# Clocks.net
KiCad netlist of a schematic drawn in Altium Designer
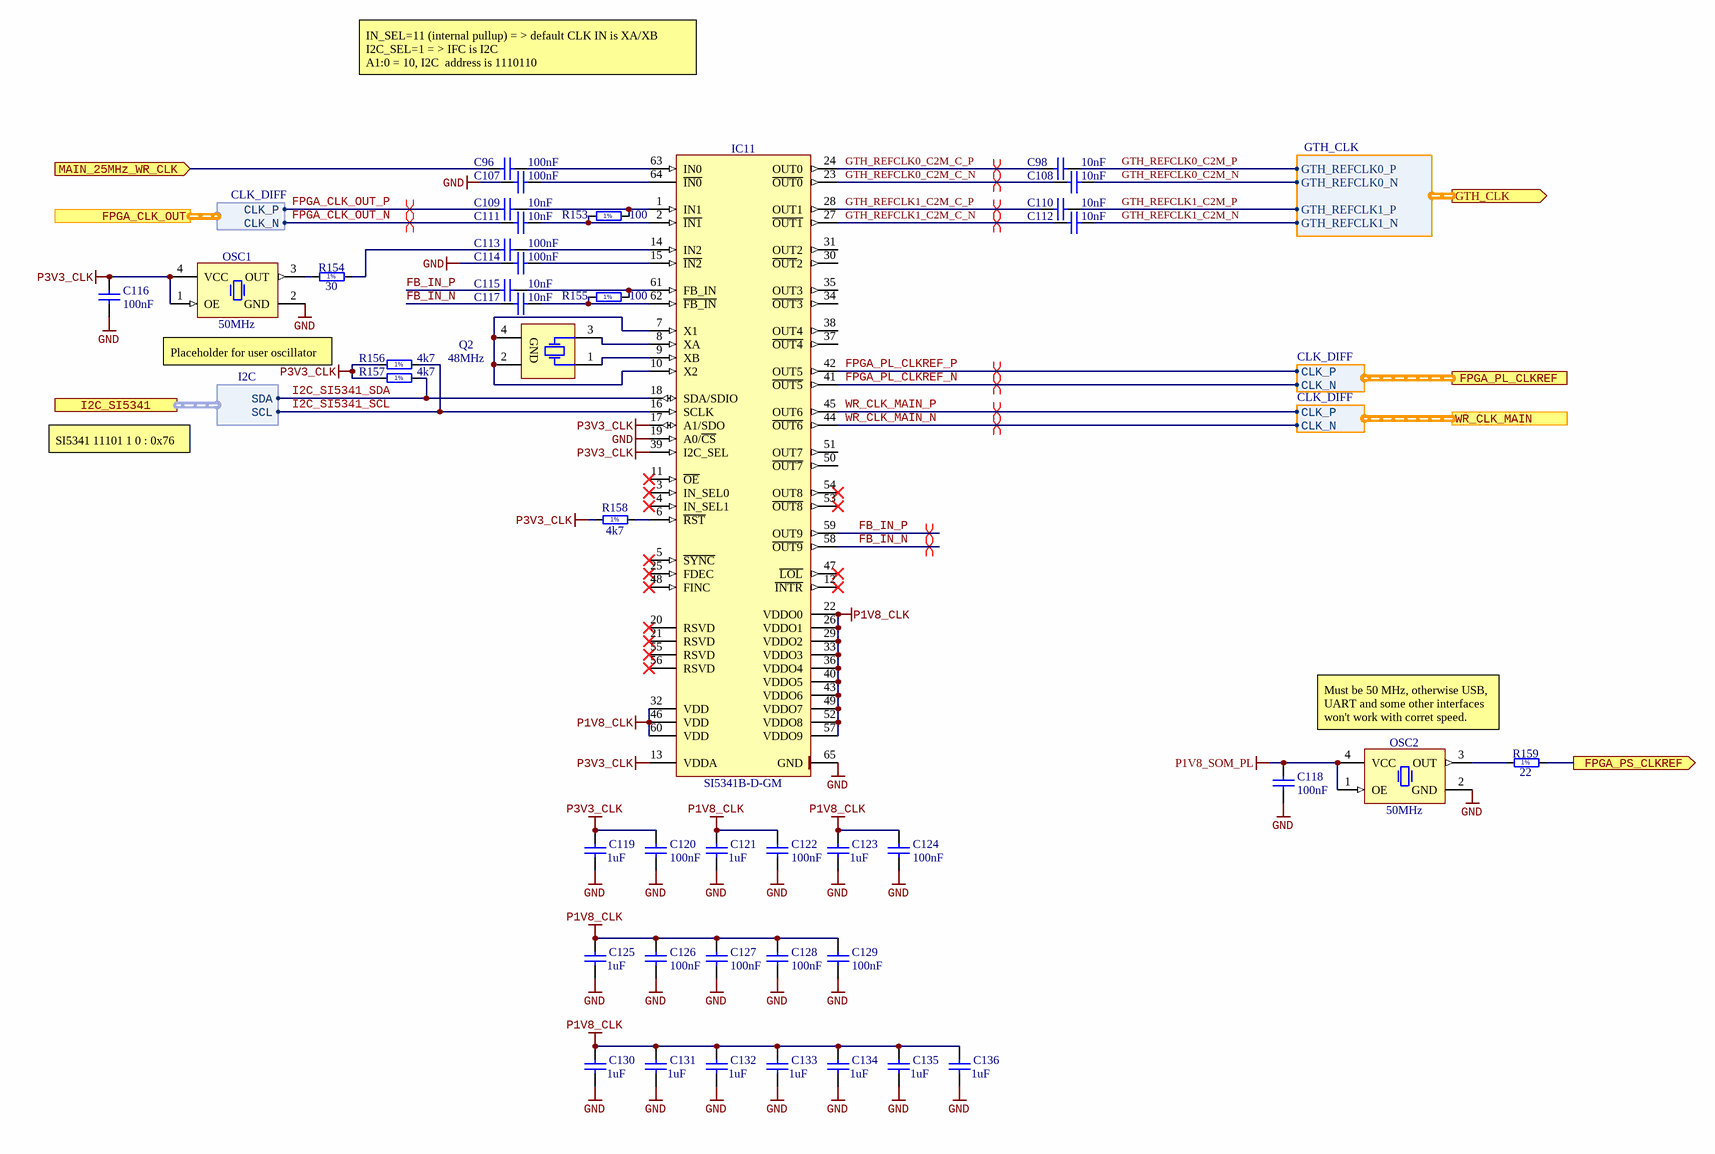
[diagram p0: Clocks.SchDoc]

(export (version "E")
  (design (tool "Eeschema 10.0.6"))
  (components
    (comp (ref "C96")
      (value "100nF")
      (footprint "CAPC1005X55N")
      (description "Non-polarised capacitor")
      (fields
        (field (name "PART NUMBER") "CC0402_100NF_16V_10%_X5R")
        (field (name "VOLTAGE") "16V")
        (field (name "AUTHOR") "CERN DEM JLC")
      )
      (libsource (lib "Capacitors") (part "Capacitor - non polarized"))
    )
    (comp (ref "C98")
      (value "10nF")
      (footprint "CAPC1005X55N")
      (description "Non-polarised capacitor")
      (fields
        (field (name "PART NUMBER") "CC0402_10NF_16V_10%_X7R")
        (field (name "VOLTAGE") "16V")
        (field (name "AUTHOR") "CERN DEM JLC")
      )
      (libsource (lib "Capacitors") (part "Capacitor - non polarized"))
    )
    (comp (ref "C107")
      (value "100nF")
      (footprint "CAPC1005X55N")
      (description "Non-polarised capacitor")
      (fields
        (field (name "PART NUMBER") "CC0402_100NF_16V_10%_X5R")
        (field (name "VOLTAGE") "16V")
        (field (name "AUTHOR") "CERN DEM JLC")
      )
      (libsource (lib "Capacitors") (part "Capacitor - non polarized"))
    )
    (comp (ref "C108")
      (value "10nF")
      (footprint "CAPC1005X55N")
      (description "Non-polarised capacitor")
      (fields
        (field (name "PART NUMBER") "CC0402_10NF_16V_10%_X7R")
        (field (name "VOLTAGE") "16V")
        (field (name "AUTHOR") "CERN DEM JLC")
      )
      (libsource (lib "Capacitors") (part "Capacitor - non polarized"))
    )
    (comp (ref "C109")
      (value "10nF")
      (footprint "CAPC1005X55N")
      (description "Non-polarised capacitor")
      (fields
        (field (name "PART NUMBER") "CC0402_10NF_16V_10%_X7R")
        (field (name "VOLTAGE") "16V")
        (field (name "AUTHOR") "CERN DEM JLC")
      )
      (libsource (lib "Capacitors") (part "Capacitor - non polarized"))
    )
    (comp (ref "C110")
      (value "10nF")
      (footprint "CAPC1005X55N")
      (description "Non-polarised capacitor")
      (fields
        (field (name "PART NUMBER") "CC0402_10NF_16V_10%_X7R")
        (field (name "VOLTAGE") "16V")
        (field (name "AUTHOR") "CERN DEM JLC")
      )
      (libsource (lib "Capacitors") (part "Capacitor - non polarized"))
    )
    (comp (ref "C111")
      (value "10nF")
      (footprint "CAPC1005X55N")
      (description "Non-polarised capacitor")
      (fields
        (field (name "PART NUMBER") "CC0402_10NF_16V_10%_X7R")
        (field (name "VOLTAGE") "16V")
        (field (name "AUTHOR") "CERN DEM JLC")
      )
      (libsource (lib "Capacitors") (part "Capacitor - non polarized"))
    )
    (comp (ref "C112")
      (value "10nF")
      (footprint "CAPC1005X55N")
      (description "Non-polarised capacitor")
      (fields
        (field (name "PART NUMBER") "CC0402_10NF_16V_10%_X7R")
        (field (name "VOLTAGE") "16V")
        (field (name "AUTHOR") "CERN DEM JLC")
      )
      (libsource (lib "Capacitors") (part "Capacitor - non polarized"))
    )
    (comp (ref "C113")
      (value "100nF")
      (footprint "CAPC1005X55N")
      (description "Non-polarised capacitor")
      (fields
        (field (name "PART NUMBER") "CC0402_100NF_16V_10%_X5R")
        (field (name "VOLTAGE") "16V")
        (field (name "AUTHOR") "CERN DEM JLC")
      )
      (libsource (lib "Capacitors") (part "Capacitor - non polarized"))
    )
    (comp (ref "C114")
      (value "100nF")
      (footprint "CAPC1005X55N")
      (description "Non-polarised capacitor")
      (fields
        (field (name "PART NUMBER") "CC0402_100NF_16V_10%_X5R")
        (field (name "VOLTAGE") "16V")
        (field (name "AUTHOR") "CERN DEM JLC")
      )
      (libsource (lib "Capacitors") (part "Capacitor - non polarized"))
    )
    (comp (ref "C115")
      (value "10nF")
      (footprint "CAPC1005X55N")
      (description "Non-polarised capacitor")
      (fields
        (field (name "PART NUMBER") "CC0402_10NF_16V_10%_X7R")
        (field (name "VOLTAGE") "16V")
        (field (name "AUTHOR") "CERN DEM JLC")
      )
      (libsource (lib "Capacitors") (part "Capacitor - non polarized"))
    )
    (comp (ref "C116")
      (value "100nF")
      (footprint "CAPC1005X55N")
      (description "Non-polarised capacitor")
      (fields
        (field (name "PART NUMBER") "CC0402_100NF_16V_10%_X5R")
        (field (name "VOLTAGE") "16V")
        (field (name "AUTHOR") "CERN DEM JLC")
      )
      (libsource (lib "Capacitors") (part "Capacitor - non polarized"))
    )
    (comp (ref "C117")
      (value "10nF")
      (footprint "CAPC1005X55N")
      (description "Non-polarised capacitor")
      (fields
        (field (name "PART NUMBER") "CC0402_10NF_16V_10%_X7R")
        (field (name "VOLTAGE") "16V")
        (field (name "AUTHOR") "CERN DEM JLC")
      )
      (libsource (lib "Capacitors") (part "Capacitor - non polarized"))
    )
    (comp (ref "C118")
      (value "100nF")
      (footprint "CAPC1005X55N")
      (description "Non-polarised capacitor")
      (fields
        (field (name "PART NUMBER") "CC0402_100NF_16V_10%_X5R")
        (field (name "VOLTAGE") "16V")
        (field (name "AUTHOR") "CERN DEM JLC")
      )
      (libsource (lib "Capacitors") (part "Capacitor - non polarized"))
    )
    (comp (ref "C119")
      (value "1uF")
      (footprint "CAPC1005X55N")
      (description "Non-polarised capacitor")
      (fields
        (field (name "PART NUMBER") "CC0402_1UF_16V_10%_X5R")
        (field (name "VOLTAGE") "16V")
        (field (name "AUTHOR") "CERN DEM JLC")
      )
      (libsource (lib "Capacitors") (part "Capacitor - non polarized"))
    )
    (comp (ref "C120")
      (value "100nF")
      (footprint "CAPC1005X55N")
      (description "Non-polarised capacitor")
      (fields
        (field (name "PART NUMBER") "CC0402_100NF_16V_10%_X5R")
        (field (name "VOLTAGE") "16V")
        (field (name "AUTHOR") "CERN DEM JLC")
      )
      (libsource (lib "Capacitors") (part "Capacitor - non polarized"))
    )
    (comp (ref "C121")
      (value "1uF")
      (footprint "CAPC1005X55N")
      (description "Non-polarised capacitor")
      (fields
        (field (name "PART NUMBER") "CC0402_1UF_16V_10%_X5R")
        (field (name "VOLTAGE") "16V")
        (field (name "AUTHOR") "CERN DEM JLC")
      )
      (libsource (lib "Capacitors") (part "Capacitor - non polarized"))
    )
    (comp (ref "C122")
      (value "100nF")
      (footprint "CAPC1005X55N")
      (description "Non-polarised capacitor")
      (fields
        (field (name "PART NUMBER") "CC0402_100NF_16V_10%_X5R")
        (field (name "VOLTAGE") "16V")
        (field (name "AUTHOR") "CERN DEM JLC")
      )
      (libsource (lib "Capacitors") (part "Capacitor - non polarized"))
    )
    (comp (ref "C123")
      (value "1uF")
      (footprint "CAPC1005X55N")
      (description "Non-polarised capacitor")
      (fields
        (field (name "PART NUMBER") "CC0402_1UF_16V_10%_X5R")
        (field (name "VOLTAGE") "16V")
        (field (name "AUTHOR") "CERN DEM JLC")
      )
      (libsource (lib "Capacitors") (part "Capacitor - non polarized"))
    )
    (comp (ref "C124")
      (value "100nF")
      (footprint "CAPC1005X55N")
      (description "Non-polarised capacitor")
      (fields
        (field (name "PART NUMBER") "CC0402_100NF_16V_10%_X5R")
        (field (name "VOLTAGE") "16V")
        (field (name "AUTHOR") "CERN DEM JLC")
      )
      (libsource (lib "Capacitors") (part "Capacitor - non polarized"))
    )
    (comp (ref "C125")
      (value "1uF")
      (footprint "CAPC1005X55N")
      (description "Non-polarised capacitor")
      (fields
        (field (name "PART NUMBER") "CC0402_1UF_16V_10%_X5R")
        (field (name "VOLTAGE") "16V")
        (field (name "AUTHOR") "CERN DEM JLC")
      )
      (libsource (lib "Capacitors") (part "Capacitor - non polarized"))
    )
    (comp (ref "C126")
      (value "100nF")
      (footprint "CAPC1005X55N")
      (description "Non-polarised capacitor")
      (fields
        (field (name "PART NUMBER") "CC0402_100NF_16V_10%_X5R")
        (field (name "VOLTAGE") "16V")
        (field (name "AUTHOR") "CERN DEM JLC")
      )
      (libsource (lib "Capacitors") (part "Capacitor - non polarized"))
    )
    (comp (ref "C127")
      (value "100nF")
      (footprint "CAPC1005X55N")
      (description "Non-polarised capacitor")
      (fields
        (field (name "PART NUMBER") "CC0402_100NF_16V_10%_X5R")
        (field (name "VOLTAGE") "16V")
        (field (name "AUTHOR") "CERN DEM JLC")
      )
      (libsource (lib "Capacitors") (part "Capacitor - non polarized"))
    )
    (comp (ref "C128")
      (value "100nF")
      (footprint "CAPC1005X55N")
      (description "Non-polarised capacitor")
      (fields
        (field (name "PART NUMBER") "CC0402_100NF_16V_10%_X5R")
        (field (name "VOLTAGE") "16V")
        (field (name "AUTHOR") "CERN DEM JLC")
      )
      (libsource (lib "Capacitors") (part "Capacitor - non polarized"))
    )
    (comp (ref "C129")
      (value "100nF")
      (footprint "CAPC1005X55N")
      (description "Non-polarised capacitor")
      (fields
        (field (name "PART NUMBER") "CC0402_100NF_16V_10%_X5R")
        (field (name "VOLTAGE") "16V")
        (field (name "AUTHOR") "CERN DEM JLC")
      )
      (libsource (lib "Capacitors") (part "Capacitor - non polarized"))
    )
    (comp (ref "C130")
      (value "1uF")
      (footprint "CAPC1005X55N")
      (description "Non-polarised capacitor")
      (fields
        (field (name "PART NUMBER") "CC0402_1UF_16V_10%_X5R")
        (field (name "VOLTAGE") "16V")
        (field (name "AUTHOR") "CERN DEM JLC")
      )
      (libsource (lib "Capacitors") (part "Capacitor - non polarized"))
    )
    (comp (ref "C131")
      (value "1uF")
      (footprint "CAPC1005X55N")
      (description "Non-polarised capacitor")
      (fields
        (field (name "PART NUMBER") "CC0402_1UF_16V_10%_X5R")
        (field (name "VOLTAGE") "16V")
        (field (name "AUTHOR") "CERN DEM JLC")
      )
      (libsource (lib "Capacitors") (part "Capacitor - non polarized"))
    )
    (comp (ref "C132")
      (value "1uF")
      (footprint "CAPC1005X55N")
      (description "Non-polarised capacitor")
      (fields
        (field (name "PART NUMBER") "CC0402_1UF_16V_10%_X5R")
        (field (name "VOLTAGE") "16V")
        (field (name "AUTHOR") "CERN DEM JLC")
      )
      (libsource (lib "Capacitors") (part "Capacitor - non polarized"))
    )
    (comp (ref "C133")
      (value "1uF")
      (footprint "CAPC1005X55N")
      (description "Non-polarised capacitor")
      (fields
        (field (name "PART NUMBER") "CC0402_1UF_16V_10%_X5R")
        (field (name "VOLTAGE") "16V")
        (field (name "AUTHOR") "CERN DEM JLC")
      )
      (libsource (lib "Capacitors") (part "Capacitor - non polarized"))
    )
    (comp (ref "C134")
      (value "1uF")
      (footprint "CAPC1005X55N")
      (description "Non-polarised capacitor")
      (fields
        (field (name "PART NUMBER") "CC0402_1UF_16V_10%_X5R")
        (field (name "VOLTAGE") "16V")
        (field (name "AUTHOR") "CERN DEM JLC")
      )
      (libsource (lib "Capacitors") (part "Capacitor - non polarized"))
    )
    (comp (ref "C135")
      (value "1uF")
      (footprint "CAPC1005X55N")
      (description "Non-polarised capacitor")
      (fields
        (field (name "PART NUMBER") "CC0402_1UF_16V_10%_X5R")
        (field (name "VOLTAGE") "16V")
        (field (name "AUTHOR") "CERN DEM JLC")
      )
      (libsource (lib "Capacitors") (part "Capacitor - non polarized"))
    )
    (comp (ref "C136")
      (value "1uF")
      (footprint "CAPC1005X55N")
      (description "Non-polarised capacitor")
      (fields
        (field (name "PART NUMBER") "CC0402_1UF_16V_10%_X5R")
        (field (name "VOLTAGE") "16V")
        (field (name "AUTHOR") "CERN DEM JLC")
      )
      (libsource (lib "Capacitors") (part "Capacitor - non polarized"))
    )
    (comp (ref "IC11")
      (value "SI5341B-D-GM")
      (footprint "QFN50P900X900X90-65N-S530")
      (description "Low-Jitter, 10-Output, Any-Frequency, Any-Output Clock Generator")
      (fields (field (name "MANUFACTURER") "SILICON LABS") (field (name "AUTHOR") "CERN DEM BC"))
      (libsource (lib "ICs And Semiconductors") (part "SI5341"))
    )
    (comp (ref "OSC1")
      (value "50MHz")
      (footprint "OSC_EPSON_SG-8018CE")
      (description "Oscillator 4 pins 1=OE 2=GND 3=OUT 4=VCC")
      (fields
        (field (name "PART NUMBER") "OSC_50MHZ_EPSON_SG-8018CE")
        (field (name "MANUFACTURER") "EPSON SEIKO")
        (field (name "AUTHOR") "CERN DEM BC")
      )
      (libsource (lib "ICs And Semiconductors") (part "Oscillator 1OE 2GND 3OUT 4VCC"))
    )
    (comp (ref "OSC2")
      (value "50MHz")
      (footprint "OSC_EPSON_SG-8018CE")
      (description "Oscillator 4 pins 1=OE 2=GND 3=OUT 4=VCC")
      (fields
        (field (name "PART NUMBER") "OSC_50MHZ_EPSON_SG-8018CE")
        (field (name "MANUFACTURER") "EPSON SEIKO")
        (field (name "AUTHOR") "CERN DEM BC")
      )
      (libsource (lib "ICs And Semiconductors") (part "Oscillator 1OE 2GND 3OUT 4VCC"))
    )
    (comp (ref "Q2")
      (value "48MHz")
      (footprint "XTAL_TXC_7M")
      (description "Crystal 4 pins 1=XTAL Control 2=GND3=XTAL 4=GND")
      (fields
        (field (name "PART NUMBER") "XTAL_48MHZ_TXC_7M-48.000MAHV")
        (field (name "MANUFACTURER") "TXC CORPORATION")
        (field (name "AUTHOR") "CERN DEM MR")
      )
      (libsource (lib "ICs And Semiconductors") (part "Quartz Crystal 1X 2GND 3X 4GND"))
    )
    (comp (ref "R153")
      (value "100")
      (footprint "RESC1005X40N")
      (description "Resistor - 1%")
      (fields
        (field (name "PART NUMBER") "R0402_100R_1%_0.0625W_100PPM")
        (field (name "POWER") "0.0625W")
        (field (name "AUTHOR") "CERN DEM JLC")
      )
      (libsource (lib "Resistors") (part "Resistor - 1%"))
    )
    (comp (ref "R154")
      (value "30")
      (footprint "RESC1005X40N")
      (description "Resistor - 1%")
      (fields
        (field (name "PART NUMBER") "R0402_30R_1%_0.0625W_100PPM")
        (field (name "POWER") "0.0625W")
        (field (name "AUTHOR") "CERN DEM JLC")
      )
      (libsource (lib "Resistors") (part "Resistor - 1%"))
    )
    (comp (ref "R155")
      (value "100")
      (footprint "RESC1005X40N")
      (description "Resistor - 1%")
      (fields
        (field (name "PART NUMBER") "R0402_100R_1%_0.0625W_100PPM")
        (field (name "POWER") "0.0625W")
        (field (name "AUTHOR") "CERN DEM JLC")
      )
      (libsource (lib "Resistors") (part "Resistor - 1%"))
    )
    (comp (ref "R156")
      (value "4k7")
      (footprint "RESC1005X40N")
      (description "Resistor - 1%")
      (fields
        (field (name "PART NUMBER") "R0402_4K7_1%_0.0625W_100PPM")
        (field (name "POWER") "0.0625W")
        (field (name "AUTHOR") "CERN DEM JLC")
      )
      (libsource (lib "Resistors") (part "Resistor - 1%"))
    )
    (comp (ref "R157")
      (value "4k7")
      (footprint "RESC1005X40N")
      (description "Resistor - 1%")
      (fields
        (field (name "PART NUMBER") "R0402_4K7_1%_0.0625W_100PPM")
        (field (name "POWER") "0.0625W")
        (field (name "AUTHOR") "CERN DEM JLC")
      )
      (libsource (lib "Resistors") (part "Resistor - 1%"))
    )
    (comp (ref "R158")
      (value "4k7")
      (footprint "RESC1005X40N")
      (description "Resistor - 1%")
      (fields
        (field (name "PART NUMBER") "R0402_4K7_1%_0.0625W_100PPM")
        (field (name "POWER") "0.0625W")
        (field (name "AUTHOR") "CERN DEM JLC")
      )
      (libsource (lib "Resistors") (part "Resistor - 1%"))
    )
    (comp (ref "R159")
      (value "22")
      (footprint "RESC1005X40N")
      (description "Resistor - 1%")
      (fields
        (field (name "PART NUMBER") "R0402_22R_1%_0.0625W_100PPM")
        (field (name "POWER") "0.0625W")
        (field (name "AUTHOR") "CERN DEM JLC")
      )
      (libsource (lib "Resistors") (part "Resistor - 1%"))
    )
  )
  (nets
    (net (code "5") (name "/FB_IN_N") (class "Default")
      (node (ref "C117") (pin "2") (pinfunction "2_2") (pintype "passive"))
      (node (ref "IC11") (pin "58") (pinfunction "~{OUT9}_58") (pintype "output"))
    )
    (net (code "6") (name "/FB_IN_P") (class "Default")
      (node (ref "C115") (pin "2") (pinfunction "2_2") (pintype "passive"))
      (node (ref "IC11") (pin "59") (pinfunction "OUT9_59") (pintype "output"))
    )
    (net (code "7") (name "/FPGA_CLK_OUT_N") (class "Default")
      (node (ref "C111") (pin "2") (pinfunction "2_2") (pintype "passive"))
    )
    (net (code "8") (name "/FPGA_CLK_OUT_P") (class "Default")
      (node (ref "C109") (pin "2") (pinfunction "2_2") (pintype "passive"))
    )
    (net (code "9") (name "/FPGA_PL_CLKREF_N") (class "Default")
      (node (ref "IC11") (pin "41") (pinfunction "~{OUT5}_41") (pintype "output"))
    )
    (net (code "10") (name "/FPGA_PL_CLKREF_P") (class "Default")
      (node (ref "IC11") (pin "42") (pinfunction "OUT5_42") (pintype "output"))
    )
    (net (code "11") (name "/FPGA_PS_CLKREF") (class "Default")
      (node (ref "R159") (pin "2") (pinfunction "2_2") (pintype "passive"))
    )
    (net (code "12") (name "/GTH_REFCLK0_C2M_C_N") (class "Default")
      (node (ref "C108") (pin "2") (pinfunction "2_2") (pintype "passive"))
      (node (ref "IC11") (pin "23") (pinfunction "~{OUT0}_23") (pintype "output"))
    )
    (net (code "13") (name "/GTH_REFCLK0_C2M_C_P") (class "Default")
      (node (ref "C98") (pin "2") (pinfunction "2_2") (pintype "passive"))
      (node (ref "IC11") (pin "24") (pinfunction "OUT0_24") (pintype "output"))
    )
    (net (code "14") (name "/GTH_REFCLK0_C2M_N") (class "Default")
      (node (ref "C108") (pin "1") (pinfunction "1_1") (pintype "passive"))
    )
    (net (code "15") (name "/GTH_REFCLK0_C2M_P") (class "Default")
      (node (ref "C98") (pin "1") (pinfunction "1_1") (pintype "passive"))
    )
    (net (code "16") (name "/GTH_REFCLK1_C2M_C_N") (class "Default")
      (node (ref "C112") (pin "2") (pinfunction "2_2") (pintype "passive"))
      (node (ref "IC11") (pin "27") (pinfunction "~{OUT1}_27") (pintype "output"))
    )
    (net (code "17") (name "/GTH_REFCLK1_C2M_C_P") (class "Default")
      (node (ref "C110") (pin "2") (pinfunction "2_2") (pintype "passive"))
      (node (ref "IC11") (pin "28") (pinfunction "OUT1_28") (pintype "output"))
    )
    (net (code "18") (name "/GTH_REFCLK1_C2M_N") (class "Default")
      (node (ref "C112") (pin "1") (pinfunction "1_1") (pintype "passive"))
    )
    (net (code "19") (name "/GTH_REFCLK1_C2M_P") (class "Default")
      (node (ref "C110") (pin "1") (pinfunction "1_1") (pintype "passive"))
    )
    (net (code "20") (name "/I2C_SI5341_SCL") (class "Default")
      (node (ref "IC11") (pin "16") (pinfunction "SCLK_16") (pintype "input"))
      (node (ref "R156") (pin "2") (pinfunction "2_2") (pintype "passive"))
    )
    (net (code "21") (name "/I2C_SI5341_SDA") (class "Default")
      (node (ref "IC11") (pin "18") (pinfunction "SDA/SDIO_18") (pintype "bidirectional"))
      (node (ref "R157") (pin "2") (pinfunction "2_2") (pintype "passive"))
    )
    (net (code "22") (name "/MAIN_25MHz_WR_CLK") (class "Default")
      (node (ref "C96") (pin "2") (pinfunction "2_2") (pintype "passive"))
    )
    (net (code "23") (name "/WR_CLK_MAIN_N") (class "Default")
      (node (ref "IC11") (pin "44") (pinfunction "~{OUT6}_44") (pintype "output"))
    )
    (net (code "24") (name "/WR_CLK_MAIN_P") (class "Default")
      (node (ref "IC11") (pin "45") (pinfunction "OUT6_45") (pintype "output"))
    )
    (net (code "28") (name "GND") (class "Default")
      (node (ref "C107") (pin "2") (pinfunction "2_2") (pintype "passive"))
      (node (ref "C114") (pin "2") (pinfunction "2_2") (pintype "passive"))
      (node (ref "C116") (pin "1") (pinfunction "1_1") (pintype "passive"))
      (node (ref "C118") (pin "1") (pinfunction "1_1") (pintype "passive"))
      (node (ref "C119") (pin "1") (pinfunction "1_1") (pintype "passive"))
      (node (ref "C120") (pin "1") (pinfunction "1_1") (pintype "passive"))
      (node (ref "C121") (pin "1") (pinfunction "1_1") (pintype "passive"))
      (node (ref "C122") (pin "1") (pinfunction "1_1") (pintype "passive"))
      (node (ref "C123") (pin "1") (pinfunction "1_1") (pintype "passive"))
      (node (ref "C124") (pin "1") (pinfunction "1_1") (pintype "passive"))
      (node (ref "C125") (pin "1") (pinfunction "1_1") (pintype "passive"))
      (node (ref "C126") (pin "1") (pinfunction "1_1") (pintype "passive"))
      (node (ref "C127") (pin "1") (pinfunction "1_1") (pintype "passive"))
      (node (ref "C128") (pin "1") (pinfunction "1_1") (pintype "passive"))
      (node (ref "C129") (pin "1") (pinfunction "1_1") (pintype "passive"))
      (node (ref "C130") (pin "1") (pinfunction "1_1") (pintype "passive"))
      (node (ref "C131") (pin "1") (pinfunction "1_1") (pintype "passive"))
      (node (ref "C132") (pin "1") (pinfunction "1_1") (pintype "passive"))
      (node (ref "C133") (pin "1") (pinfunction "1_1") (pintype "passive"))
      (node (ref "C134") (pin "1") (pinfunction "1_1") (pintype "passive"))
      (node (ref "C135") (pin "1") (pinfunction "1_1") (pintype "passive"))
      (node (ref "C136") (pin "1") (pinfunction "1_1") (pintype "passive"))
      (node (ref "IC11") (pin "19") (pinfunction "A0/~{CS}_19") (pintype "input"))
      (node (ref "IC11") (pin "65") (pinfunction "GND_65") (pintype "power_in"))
      (node (ref "OSC1") (pin "2") (pinfunction "GND_2") (pintype "power_in"))
      (node (ref "OSC2") (pin "2") (pinfunction "GND_2") (pintype "power_in"))
    )
    (net (code "29") (name "Net-(C113-Pad2)") (class "Default")
      (node (ref "C113") (pin "2") (pinfunction "2_2") (pintype "passive"))
      (node (ref "R154") (pin "2") (pinfunction "2_2") (pintype "passive"))
    )
    (net (code "30") (name "Net-(IC11-FB_IN)") (class "Default")
      (node (ref "C115") (pin "1") (pinfunction "1_1") (pintype "passive"))
      (node (ref "IC11") (pin "61") (pinfunction "FB_IN_61") (pintype "input"))
      (node (ref "R155") (pin "2") (pinfunction "2_2") (pintype "passive"))
    )
    (net (code "31") (name "Net-(IC11-IN0)") (class "Default")
      (node (ref "C96") (pin "1") (pinfunction "1_1") (pintype "passive"))
      (node (ref "IC11") (pin "63") (pinfunction "IN0_63") (pintype "input"))
    )
    (net (code "32") (name "Net-(IC11-IN1)") (class "Default")
      (node (ref "C109") (pin "1") (pinfunction "1_1") (pintype "passive"))
      (node (ref "IC11") (pin "1") (pinfunction "IN1_1") (pintype "input"))
      (node (ref "R153") (pin "2") (pinfunction "2_2") (pintype "passive"))
    )
    (net (code "33") (name "Net-(IC11-IN2)") (class "Default")
      (node (ref "C113") (pin "1") (pinfunction "1_1") (pintype "passive"))
      (node (ref "IC11") (pin "14") (pinfunction "IN2_14") (pintype "input"))
    )
    (net (code "34") (name "Net-(IC11-X1)") (class "Default")
      (node (ref "IC11") (pin "10") (pinfunction "X2_10") (pintype "input"))
      (node (ref "IC11") (pin "7") (pinfunction "X1_7") (pintype "input"))
      (node (ref "Q2") (pin "2") (pinfunction "GND_2") (pintype "power_in"))
      (node (ref "Q2") (pin "4") (pinfunction "GND_4") (pintype "power_in"))
    )
    (net (code "35") (name "Net-(IC11-XA)") (class "Default")
      (node (ref "IC11") (pin "8") (pinfunction "XA_8") (pintype "input"))
      (node (ref "Q2") (pin "3") (pinfunction "X_3") (pintype "passive"))
    )
    (net (code "36") (name "Net-(IC11-XB)") (class "Default")
      (node (ref "IC11") (pin "9") (pinfunction "XB_9") (pintype "input"))
      (node (ref "Q2") (pin "1") (pinfunction "X_1") (pintype "passive"))
    )
    (net (code "37") (name "Net-(IC11-~{FB_IN})") (class "Default")
      (node (ref "C117") (pin "1") (pinfunction "1_1") (pintype "passive"))
      (node (ref "IC11") (pin "62") (pinfunction "~{FB_IN}_62") (pintype "input"))
      (node (ref "R155") (pin "1") (pinfunction "1_1") (pintype "passive"))
    )
    (net (code "38") (name "Net-(IC11-~{IN0})") (class "Default")
      (node (ref "C107") (pin "1") (pinfunction "1_1") (pintype "passive"))
      (node (ref "IC11") (pin "64") (pinfunction "~{IN0}_64") (pintype "open_collector"))
    )
    (net (code "39") (name "Net-(IC11-~{IN1})") (class "Default")
      (node (ref "C111") (pin "1") (pinfunction "1_1") (pintype "passive"))
      (node (ref "IC11") (pin "2") (pinfunction "~{IN1}_2") (pintype "input"))
      (node (ref "R153") (pin "1") (pinfunction "1_1") (pintype "passive"))
    )
    (net (code "40") (name "Net-(IC11-~{IN2})") (class "Default")
      (node (ref "C114") (pin "1") (pinfunction "1_1") (pintype "passive"))
      (node (ref "IC11") (pin "15") (pinfunction "~{IN2}_15") (pintype "input"))
    )
    (net (code "41") (name "Net-(IC11-~{RST})") (class "Default")
      (node (ref "IC11") (pin "6") (pinfunction "~{RST}_6") (pintype "input"))
      (node (ref "R158") (pin "2") (pinfunction "2_2") (pintype "passive"))
    )
    (net (code "42") (name "Net-(OSC1-OUT)") (class "Default")
      (node (ref "OSC1") (pin "3") (pinfunction "OUT_3") (pintype "output"))
      (node (ref "R154") (pin "1") (pinfunction "1_1") (pintype "passive"))
    )
    (net (code "43") (name "Net-(OSC2-OUT)") (class "Default")
      (node (ref "OSC2") (pin "3") (pinfunction "OUT_3") (pintype "output"))
      (node (ref "R159") (pin "1") (pinfunction "1_1") (pintype "passive"))
    )
    (net (code "44") (name "P1V8_CLK") (class "Default")
      (node (ref "C121") (pin "2") (pinfunction "2_2") (pintype "passive"))
      (node (ref "C122") (pin "2") (pinfunction "2_2") (pintype "passive"))
      (node (ref "C123") (pin "2") (pinfunction "2_2") (pintype "passive"))
      (node (ref "C124") (pin "2") (pinfunction "2_2") (pintype "passive"))
      (node (ref "C125") (pin "2") (pinfunction "2_2") (pintype "passive"))
      (node (ref "C126") (pin "2") (pinfunction "2_2") (pintype "passive"))
      (node (ref "C127") (pin "2") (pinfunction "2_2") (pintype "passive"))
      (node (ref "C128") (pin "2") (pinfunction "2_2") (pintype "passive"))
      (node (ref "C129") (pin "2") (pinfunction "2_2") (pintype "passive"))
      (node (ref "C130") (pin "2") (pinfunction "2_2") (pintype "passive"))
      (node (ref "C131") (pin "2") (pinfunction "2_2") (pintype "passive"))
      (node (ref "C132") (pin "2") (pinfunction "2_2") (pintype "passive"))
      (node (ref "C133") (pin "2") (pinfunction "2_2") (pintype "passive"))
      (node (ref "C134") (pin "2") (pinfunction "2_2") (pintype "passive"))
      (node (ref "C135") (pin "2") (pinfunction "2_2") (pintype "passive"))
      (node (ref "C136") (pin "2") (pinfunction "2_2") (pintype "passive"))
      (node (ref "IC11") (pin "22") (pinfunction "VDDO0_22") (pintype "power_in"))
      (node (ref "IC11") (pin "26") (pinfunction "VDDO1_26") (pintype "power_in"))
      (node (ref "IC11") (pin "29") (pinfunction "VDDO2_29") (pintype "power_in"))
      (node (ref "IC11") (pin "32") (pinfunction "VDD_32") (pintype "power_in"))
      (node (ref "IC11") (pin "33") (pinfunction "VDDO3_33") (pintype "power_in"))
      (node (ref "IC11") (pin "36") (pinfunction "VDDO4_36") (pintype "power_in"))
      (node (ref "IC11") (pin "40") (pinfunction "VDDO5_40") (pintype "power_in"))
      (node (ref "IC11") (pin "43") (pinfunction "VDDO6_43") (pintype "power_in"))
      (node (ref "IC11") (pin "46") (pinfunction "VDD_46") (pintype "power_in"))
      (node (ref "IC11") (pin "49") (pinfunction "VDDO7_49") (pintype "power_in"))
      (node (ref "IC11") (pin "52") (pinfunction "VDDO8_52") (pintype "power_in"))
      (node (ref "IC11") (pin "57") (pinfunction "VDDO9_57") (pintype "power_in"))
      (node (ref "IC11") (pin "60") (pinfunction "VDD_60") (pintype "power_in"))
    )
    (net (code "45") (name "P1V8_SOM_PL") (class "Default")
      (node (ref "C118") (pin "2") (pinfunction "2_2") (pintype "passive"))
      (node (ref "OSC2") (pin "1") (pinfunction "OE_1") (pintype "input"))
      (node (ref "OSC2") (pin "4") (pinfunction "VCC_4") (pintype "power_in"))
    )
    (net (code "46") (name "P3V3_CLK") (class "Default")
      (node (ref "C116") (pin "2") (pinfunction "2_2") (pintype "passive"))
      (node (ref "C119") (pin "2") (pinfunction "2_2") (pintype "passive"))
      (node (ref "C120") (pin "2") (pinfunction "2_2") (pintype "passive"))
      (node (ref "IC11") (pin "13") (pinfunction "VDDA_13") (pintype "power_in"))
      (node (ref "IC11") (pin "17") (pinfunction "A1/SDO_17") (pintype "bidirectional"))
      (node (ref "IC11") (pin "39") (pinfunction "I2C_SEL_39") (pintype "input"))
      (node (ref "OSC1") (pin "1") (pinfunction "OE_1") (pintype "input"))
      (node (ref "OSC1") (pin "4") (pinfunction "VCC_4") (pintype "power_in"))
      (node (ref "R156") (pin "1") (pinfunction "1_1") (pintype "passive"))
      (node (ref "R157") (pin "1") (pinfunction "1_1") (pintype "passive"))
      (node (ref "R158") (pin "1") (pinfunction "1_1") (pintype "passive"))
    )
    (net (code "47") (name "unconnected-(IC11-FDEC-Pad25)") (class "Default")
      (node (ref "IC11") (pin "25") (pinfunction "FDEC_25") (pintype "input+no_connect"))
    )
    (net (code "48") (name "unconnected-(IC11-FINC-Pad48)") (class "Default")
      (node (ref "IC11") (pin "48") (pinfunction "FINC_48") (pintype "input+no_connect"))
    )
    (net (code "49") (name "unconnected-(IC11-IN_SEL0-Pad3)") (class "Default")
      (node (ref "IC11") (pin "3") (pinfunction "IN_SEL0_3") (pintype "input+no_connect"))
    )
    (net (code "50") (name "unconnected-(IC11-IN_SEL1-Pad4)") (class "Default")
      (node (ref "IC11") (pin "4") (pinfunction "IN_SEL1_4") (pintype "input+no_connect"))
    )
    (net (code "51") (name "unconnected-(IC11-OUT2-Pad31)") (class "Default")
      (node (ref "IC11") (pin "31") (pinfunction "OUT2_31") (pintype "output"))
    )
    (net (code "52") (name "unconnected-(IC11-OUT3-Pad35)") (class "Default")
      (node (ref "IC11") (pin "35") (pinfunction "OUT3_35") (pintype "output"))
    )
    (net (code "53") (name "unconnected-(IC11-OUT4-Pad38)") (class "Default")
      (node (ref "IC11") (pin "38") (pinfunction "OUT4_38") (pintype "output"))
    )
    (net (code "54") (name "unconnected-(IC11-OUT7-Pad51)") (class "Default")
      (node (ref "IC11") (pin "51") (pinfunction "OUT7_51") (pintype "output"))
    )
    (net (code "55") (name "unconnected-(IC11-OUT8-Pad54)") (class "Default")
      (node (ref "IC11") (pin "54") (pinfunction "OUT8_54") (pintype "output+no_connect"))
    )
    (net (code "56") (name "unconnected-(IC11-RSVD-Pad20)") (class "Default")
      (node (ref "IC11") (pin "20") (pinfunction "RSVD_20") (pintype "passive+no_connect"))
    )
    (net (code "57") (name "unconnected-(IC11-RSVD-Pad21)") (class "Default")
      (node (ref "IC11") (pin "21") (pinfunction "RSVD_21") (pintype "passive+no_connect"))
    )
    (net (code "58") (name "unconnected-(IC11-RSVD-Pad55)") (class "Default")
      (node (ref "IC11") (pin "55") (pinfunction "RSVD_55") (pintype "passive+no_connect"))
    )
    (net (code "59") (name "unconnected-(IC11-RSVD-Pad56)") (class "Default")
      (node (ref "IC11") (pin "56") (pinfunction "RSVD_56") (pintype "passive+no_connect"))
    )
    (net (code "60") (name "unconnected-(IC11-~{INTR}-Pad12)") (class "Default")
      (node (ref "IC11") (pin "12") (pinfunction "~{INTR}_12") (pintype "output+no_connect"))
    )
    (net (code "61") (name "unconnected-(IC11-~{LOL}-Pad47)") (class "Default")
      (node (ref "IC11") (pin "47") (pinfunction "~{LOL}_47") (pintype "output+no_connect"))
    )
    (net (code "62") (name "unconnected-(IC11-~{OE}-Pad11)") (class "Default")
      (node (ref "IC11") (pin "11") (pinfunction "~{OE}_11") (pintype "input+no_connect"))
    )
    (net (code "63") (name "unconnected-(IC11-~{OUT3}-Pad34)") (class "Default")
      (node (ref "IC11") (pin "34") (pinfunction "~{OUT3}_34") (pintype "output"))
    )
    (net (code "64") (name "unconnected-(IC11-~{OUT4}-Pad37)") (class "Default")
      (node (ref "IC11") (pin "37") (pinfunction "~{OUT4}_37") (pintype "output"))
    )
    (net (code "65") (name "unconnected-(IC11-~{OUT7}-Pad50)") (class "Default")
      (node (ref "IC11") (pin "50") (pinfunction "~{OUT7}_50") (pintype "output"))
    )
    (net (code "66") (name "unconnected-(IC11-~{OUT8}-Pad53)") (class "Default")
      (node (ref "IC11") (pin "53") (pinfunction "~{OUT8}_53") (pintype "output+no_connect"))
    )
    (net (code "67") (name "unconnected-(IC11-~{OUT}2-Pad30)") (class "Default")
      (node (ref "IC11") (pin "30") (pinfunction "~{OUT}2_30") (pintype "output"))
    )
    (net (code "68") (name "unconnected-(IC11-~{SYNC}-Pad5)") (class "Default")
      (node (ref "IC11") (pin "5") (pinfunction "~{SYNC}_5") (pintype "input+no_connect"))
    )
  )
)
